# Hydrophone2012.net
KiCad netlist of a schematic drawn in Altium Designer
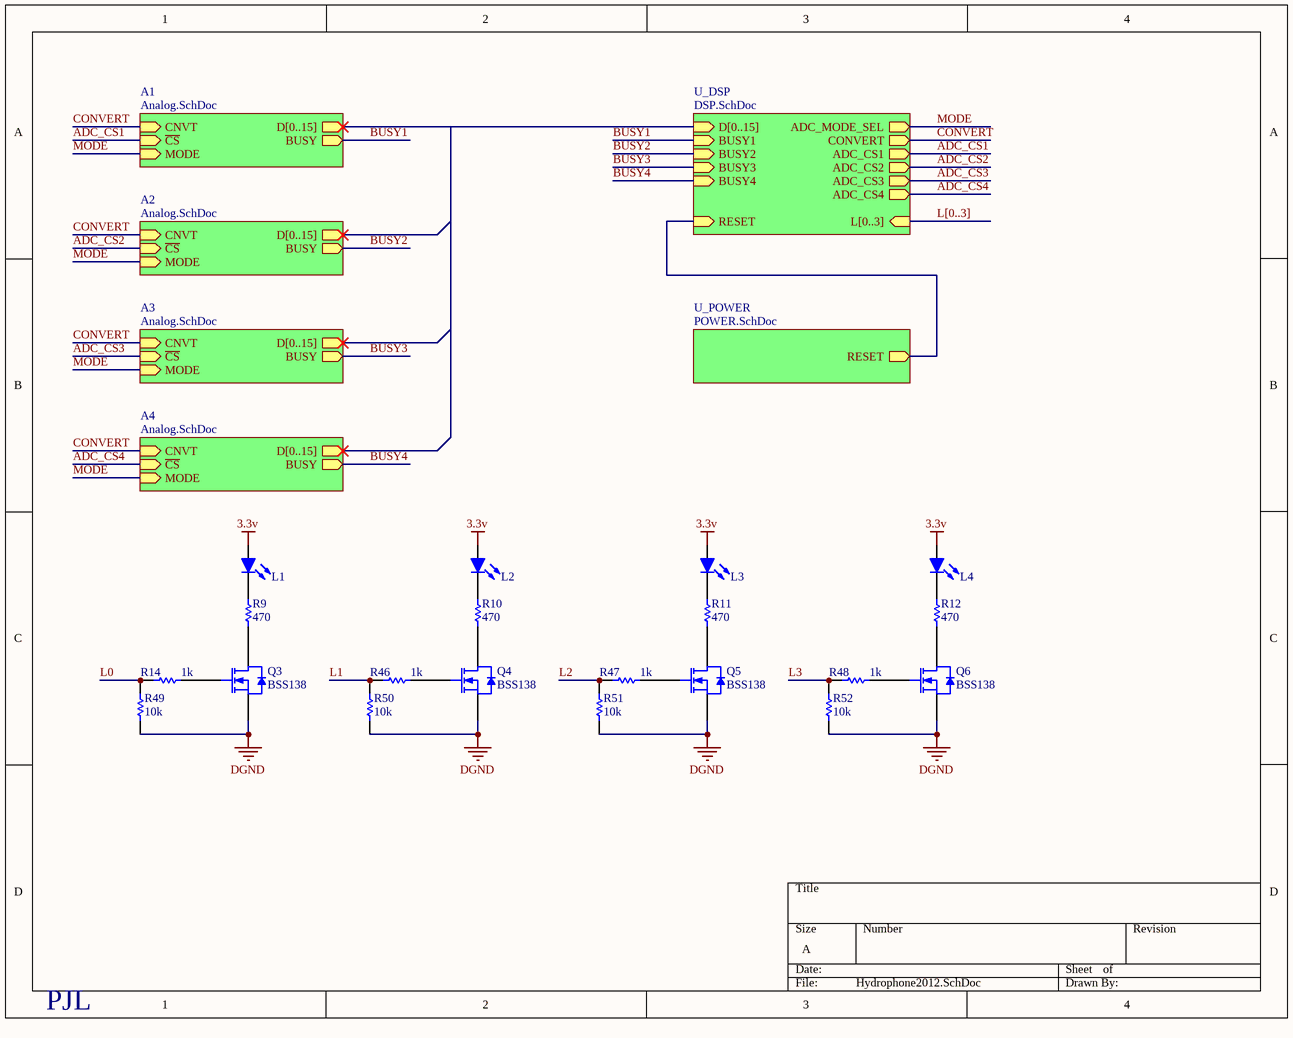
[diagram p0: Hydrophone2012.SchDoc]

(export (version "E")
  (design (tool "Eeschema 10.0.6"))
  (components
    (comp (ref "L1")
      (value "LED-RED")
      (footprint "Hydrophone:LED0805-RED")
      (description "Light Emitting Diode - RED")
      (fields
        (field (name "MANUFACTURER PART NUMBER") "LTST-C170CKT")
        (field (name "MANUFACTURER") "Lite-On Inc")
      )
      (libsource (lib "Hydrophone") (part "LED-RED"))
    )
    (comp (ref "L2")
      (value "LED-RED")
      (footprint "Hydrophone:LED0805-RED")
      (description "Light Emitting Diode - RED")
      (fields
        (field (name "MANUFACTURER PART NUMBER") "LTST-C170CKT")
        (field (name "MANUFACTURER") "Lite-On Inc")
      )
      (libsource (lib "Hydrophone") (part "LED-RED"))
    )
    (comp (ref "L3")
      (value "LED-RED")
      (footprint "Hydrophone:LED0805-RED")
      (description "Light Emitting Diode - RED")
      (fields
        (field (name "MANUFACTURER PART NUMBER") "LTST-C170CKT")
        (field (name "MANUFACTURER") "Lite-On Inc")
      )
      (libsource (lib "Hydrophone") (part "LED-RED"))
    )
    (comp (ref "L4")
      (value "LED-RED")
      (footprint "Hydrophone:LED0805-RED")
      (description "Light Emitting Diode - RED")
      (fields
        (field (name "MANUFACTURER PART NUMBER") "LTST-C170CKT")
        (field (name "MANUFACTURER") "Lite-On Inc")
      )
      (libsource (lib "Hydrophone") (part "LED-RED"))
    )
    (comp (ref "LOGO1")
      (value "UF LOGO")
      (footprint "UF LOGO-1000")
      (libsource (lib "Hydrophone") (part "UF LOGO"))
    )
    (comp (ref "LOGO2")
      (value "SubjuGator Logo")
      (footprint "SubjuGator-1200")
      (libsource (lib "Hydrophone") (part "SubjuGator Logo"))
    )
    (comp (ref "MIL")
      (value "MIL LOGO")
      (footprint "MIL LOGO - 600P")
      (libsource (lib "Hydrophone") (part "MIL LOGO"))
    )
    (comp (ref "Q3")
      (value "BSS138")
      (footprint "SOT95P237X111-3L")
      (description "200ma N-Channel Mosfet")
      (fields
        (field (name "MANUFACTURER PART NUMBER") "BSS138LT1G")
        (field (name "MANUFACTURER") "ON Semiconductor")
      )
      (libsource (lib "MyAltiumLibrary") (part "BSS138"))
    )
    (comp (ref "Q4")
      (value "BSS138")
      (footprint "SOT95P237X111-3L")
      (description "200ma N-Channel Mosfet")
      (fields
        (field (name "MANUFACTURER PART NUMBER") "BSS138LT1G")
        (field (name "MANUFACTURER") "ON Semiconductor")
      )
      (libsource (lib "MyAltiumLibrary") (part "BSS138"))
    )
    (comp (ref "Q5")
      (value "BSS138")
      (footprint "SOT95P237X111-3L")
      (description "200ma N-Channel Mosfet")
      (fields
        (field (name "MANUFACTURER PART NUMBER") "BSS138LT1G")
        (field (name "MANUFACTURER") "ON Semiconductor")
      )
      (libsource (lib "MyAltiumLibrary") (part "BSS138"))
    )
    (comp (ref "Q6")
      (value "BSS138")
      (footprint "SOT95P237X111-3L")
      (description "200ma N-Channel Mosfet")
      (fields
        (field (name "MANUFACTURER PART NUMBER") "BSS138LT1G")
        (field (name "MANUFACTURER") "ON Semiconductor")
      )
      (libsource (lib "MyAltiumLibrary") (part "BSS138"))
    )
    (comp (ref "R9")
      (value "470")
      (footprint "RESC1608XN")
      (description "RES 470 OHM .25W 5% 0603 SMD")
      (fields
        (field (name "MANUFACTURER") "Vishay Dale")
        (field (name "MANUFACTURER PART NUMBER") "CRCW0603470RJNEAHP")
      )
      (libsource (lib "SubLibrary") (part "RES-CHIP"))
    )
    (comp (ref "R10")
      (value "470")
      (footprint "RESC1608XN")
      (description "RES 470 OHM .25W 5% 0603 SMD")
      (fields
        (field (name "MANUFACTURER") "Vishay Dale")
        (field (name "MANUFACTURER PART NUMBER") "CRCW0603470RJNEAHP")
      )
      (libsource (lib "SubLibrary") (part "RES-CHIP"))
    )
    (comp (ref "R11")
      (value "470")
      (footprint "RESC1608XN")
      (description "RES 470 OHM .25W 5% 0603 SMD")
      (fields
        (field (name "MANUFACTURER") "Vishay Dale")
        (field (name "MANUFACTURER PART NUMBER") "CRCW0603470RJNEAHP")
      )
      (libsource (lib "SubLibrary") (part "RES-CHIP"))
    )
    (comp (ref "R12")
      (value "470")
      (footprint "RESC1608XN")
      (description "RES 470 OHM .25W 5% 0603 SMD")
      (fields
        (field (name "MANUFACTURER") "Vishay Dale")
        (field (name "MANUFACTURER PART NUMBER") "CRCW0603470RJNEAHP")
      )
      (libsource (lib "SubLibrary") (part "RES-CHIP"))
    )
    (comp (ref "R14")
      (value "1k")
      (footprint "RESC1608XL")
      (description "Resistor Chip")
      (fields (field (name "MANUFACTURER") "Yageo") (field (name "TOLERANCE") "±5%"))
      (libsource (lib "SubLibrary") (part "RES-CHIP"))
    )
    (comp (ref "R46")
      (value "1k")
      (footprint "RESC1608XL")
      (description "Resistor Chip")
      (fields (field (name "MANUFACTURER") "Yageo") (field (name "TOLERANCE") "±5%"))
      (libsource (lib "SubLibrary") (part "RES-CHIP"))
    )
    (comp (ref "R47")
      (value "1k")
      (footprint "RESC1608XL")
      (description "Resistor Chip")
      (fields (field (name "MANUFACTURER") "Yageo") (field (name "TOLERANCE") "±5%"))
      (libsource (lib "SubLibrary") (part "RES-CHIP"))
    )
    (comp (ref "R48")
      (value "1k")
      (footprint "RESC1608XL")
      (description "Resistor Chip")
      (fields (field (name "MANUFACTURER") "Yageo") (field (name "TOLERANCE") "±5%"))
      (libsource (lib "SubLibrary") (part "RES-CHIP"))
    )
    (comp (ref "R49")
      (value "10k")
      (footprint "RESC1608XL")
      (description "Resistor Chip")
      (fields
        (field (name "MANUFACTURER") "Yageo")
        (field (name "MANUFACTURER PART NUMBER") "RC0603JR-0710KL")
      )
      (libsource (lib "SubLibrary") (part "RES-CHIP"))
    )
    (comp (ref "R50")
      (value "10k")
      (footprint "RESC1608XL")
      (description "Resistor Chip")
      (fields
        (field (name "MANUFACTURER") "Yageo")
        (field (name "MANUFACTURER PART NUMBER") "RC0603JR-0710KL")
      )
      (libsource (lib "SubLibrary") (part "RES-CHIP"))
    )
    (comp (ref "R51")
      (value "10k")
      (footprint "RESC1608XL")
      (description "Resistor Chip")
      (fields
        (field (name "MANUFACTURER") "Yageo")
        (field (name "MANUFACTURER PART NUMBER") "RC0603JR-0710KL")
      )
      (libsource (lib "SubLibrary") (part "RES-CHIP"))
    )
    (comp (ref "R52")
      (value "10k")
      (footprint "RESC1608XL")
      (description "Resistor Chip")
      (fields
        (field (name "MANUFACTURER") "Yageo")
        (field (name "MANUFACTURER PART NUMBER") "RC0603JR-0710KL")
      )
      (libsource (lib "SubLibrary") (part "RES-CHIP"))
    )
  )
  (nets
    (net (code "14") (name "/L0") (class "Default")
      (node (ref "R14") (pin "1") (pinfunction "1_1") (pintype "passive"))
      (node (ref "R49") (pin "1") (pinfunction "1_1") (pintype "passive"))
    )
    (net (code "15") (name "/L1") (class "Default")
      (node (ref "R46") (pin "1") (pinfunction "1_1") (pintype "passive"))
      (node (ref "R50") (pin "1") (pinfunction "1_1") (pintype "passive"))
    )
    (net (code "16") (name "/L2") (class "Default")
      (node (ref "R47") (pin "1") (pinfunction "1_1") (pintype "passive"))
      (node (ref "R51") (pin "1") (pinfunction "1_1") (pintype "passive"))
    )
    (net (code "17") (name "/L3") (class "Default")
      (node (ref "R48") (pin "1") (pinfunction "1_1") (pintype "passive"))
      (node (ref "R52") (pin "1") (pinfunction "1_1") (pintype "passive"))
    )
    (net (code "21") (name "3.3v") (class "Default")
      (node (ref "L1") (pin "2") (pinfunction "A_2") (pintype "passive"))
      (node (ref "L2") (pin "2") (pinfunction "A_2") (pintype "passive"))
      (node (ref "L3") (pin "2") (pinfunction "A_2") (pintype "passive"))
      (node (ref "L4") (pin "2") (pinfunction "A_2") (pintype "passive"))
    )
    (net (code "22") (name "DGND") (class "Default")
      (node (ref "Q3") (pin "2") (pinfunction "S_2") (pintype "passive"))
      (node (ref "Q4") (pin "2") (pinfunction "S_2") (pintype "passive"))
      (node (ref "Q5") (pin "2") (pinfunction "S_2") (pintype "passive"))
      (node (ref "Q6") (pin "2") (pinfunction "S_2") (pintype "passive"))
      (node (ref "R49") (pin "2") (pinfunction "2_2") (pintype "passive"))
      (node (ref "R50") (pin "2") (pinfunction "2_2") (pintype "passive"))
      (node (ref "R51") (pin "2") (pinfunction "2_2") (pintype "passive"))
      (node (ref "R52") (pin "2") (pinfunction "2_2") (pintype "passive"))
    )
    (net (code "23") (name "Net-(L1-K)") (class "Default")
      (node (ref "L1") (pin "1") (pinfunction "K_1") (pintype "passive"))
      (node (ref "R9") (pin "2") (pinfunction "2_2") (pintype "passive"))
    )
    (net (code "24") (name "Net-(L2-K)") (class "Default")
      (node (ref "L2") (pin "1") (pinfunction "K_1") (pintype "passive"))
      (node (ref "R10") (pin "2") (pinfunction "2_2") (pintype "passive"))
    )
    (net (code "25") (name "Net-(L3-K)") (class "Default")
      (node (ref "L3") (pin "1") (pinfunction "K_1") (pintype "passive"))
      (node (ref "R11") (pin "2") (pinfunction "2_2") (pintype "passive"))
    )
    (net (code "26") (name "Net-(L4-K)") (class "Default")
      (node (ref "L4") (pin "1") (pinfunction "K_1") (pintype "passive"))
      (node (ref "R12") (pin "2") (pinfunction "2_2") (pintype "passive"))
    )
    (net (code "27") (name "Net-(Q3-D)") (class "Default")
      (node (ref "Q3") (pin "3") (pinfunction "D_3") (pintype "passive"))
      (node (ref "R9") (pin "1") (pinfunction "1_1") (pintype "passive"))
    )
    (net (code "28") (name "Net-(Q3-G)") (class "Default")
      (node (ref "Q3") (pin "1") (pinfunction "G_1") (pintype "passive"))
      (node (ref "R14") (pin "2") (pinfunction "2_2") (pintype "passive"))
    )
    (net (code "29") (name "Net-(Q4-D)") (class "Default")
      (node (ref "Q4") (pin "3") (pinfunction "D_3") (pintype "passive"))
      (node (ref "R10") (pin "1") (pinfunction "1_1") (pintype "passive"))
    )
    (net (code "30") (name "Net-(Q4-G)") (class "Default")
      (node (ref "Q4") (pin "1") (pinfunction "G_1") (pintype "passive"))
      (node (ref "R46") (pin "2") (pinfunction "2_2") (pintype "passive"))
    )
    (net (code "31") (name "Net-(Q5-D)") (class "Default")
      (node (ref "Q5") (pin "3") (pinfunction "D_3") (pintype "passive"))
      (node (ref "R11") (pin "1") (pinfunction "1_1") (pintype "passive"))
    )
    (net (code "32") (name "Net-(Q5-G)") (class "Default")
      (node (ref "Q5") (pin "1") (pinfunction "G_1") (pintype "passive"))
      (node (ref "R47") (pin "2") (pinfunction "2_2") (pintype "passive"))
    )
    (net (code "33") (name "Net-(Q6-D)") (class "Default")
      (node (ref "Q6") (pin "3") (pinfunction "D_3") (pintype "passive"))
      (node (ref "R12") (pin "1") (pinfunction "1_1") (pintype "passive"))
    )
    (net (code "34") (name "Net-(Q6-G)") (class "Default")
      (node (ref "Q6") (pin "1") (pinfunction "G_1") (pintype "passive"))
      (node (ref "R48") (pin "2") (pinfunction "2_2") (pintype "passive"))
    )
  )
)
